# Enerfi.net
KiCad netlist of a schematic drawn in Altium Designer
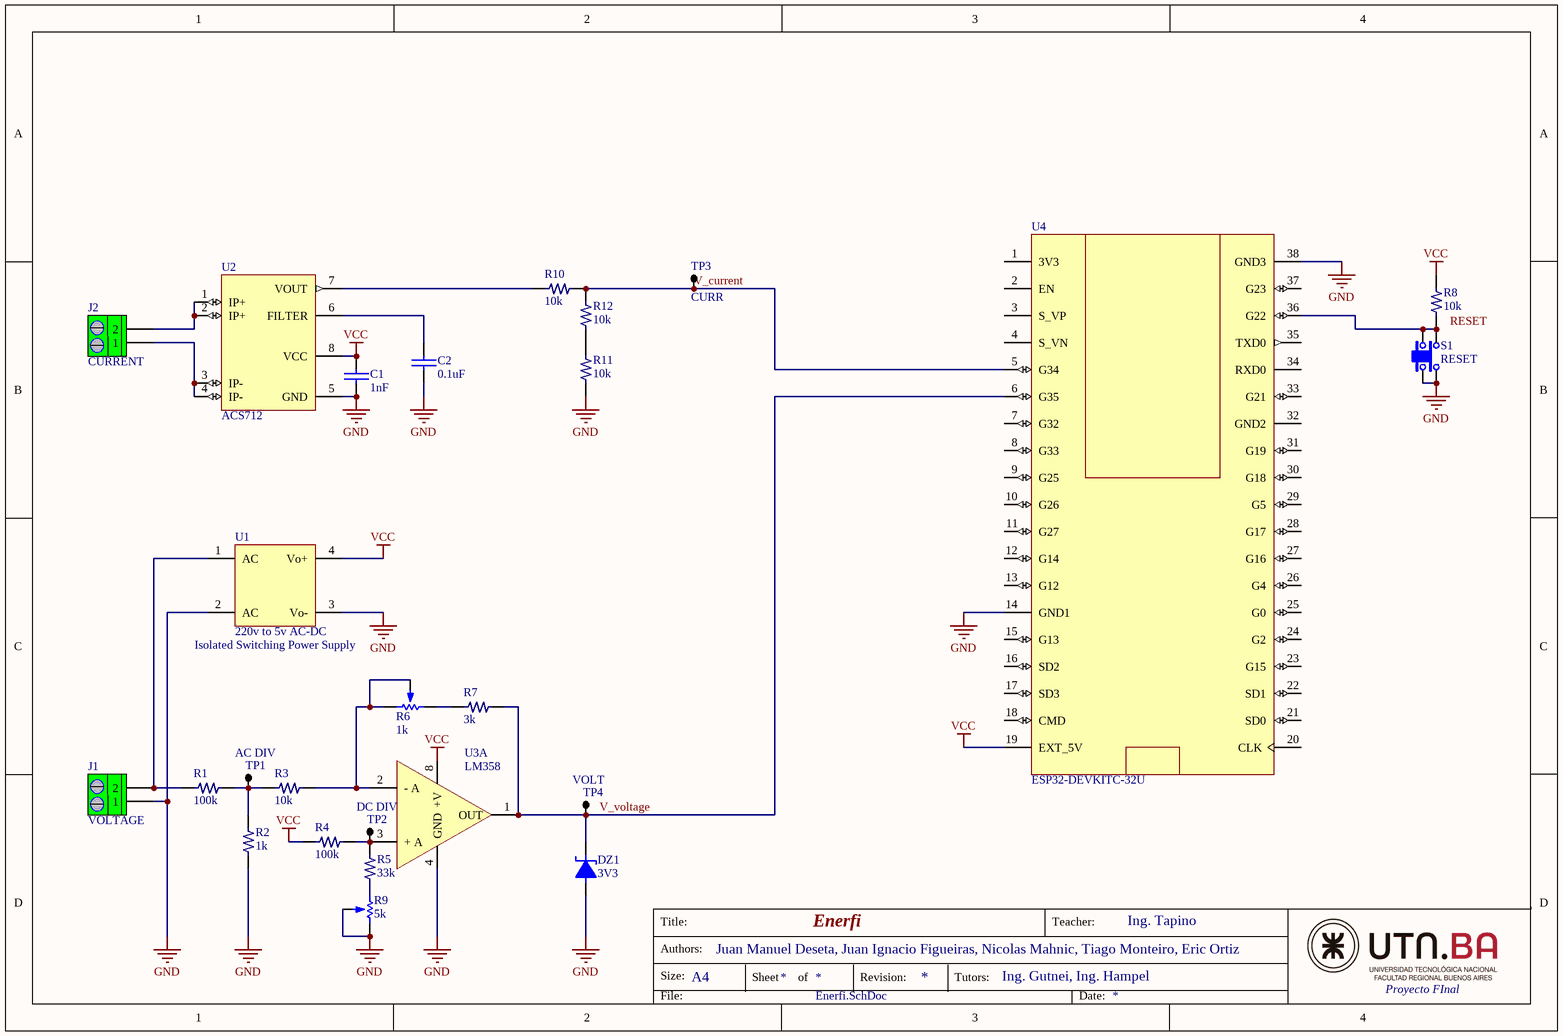
[diagram p0: Enerfi.SchDoc]

(export (version "E")
  (design (tool "Eeschema 10.0.6"))
  (components
    (comp (ref "C1") (value "1nF") (footprint "C0805-0.80") (libsource (lib "EnerfiLib") (part "CAP")))
    (comp (ref "C2") (value "0.1uF") (footprint "C0805-0.80") (libsource (lib "EnerfiLib") (part "CAP")))
    (comp (ref "DZ1") (value "3V3") (footprint "DO35") (libsource (lib "EnerfiLib") (part "DIODO ZENER")))
    (comp (ref "J1")
      (value "VOLTAGE")
      (footprint "BORNERA2")
      (libsource (lib "EnerfiLib") (part "BORNERA 2_V"))
    )
    (comp (ref "J2")
      (value "CURRENT")
      (footprint "BORNERA2")
      (libsource (lib "EnerfiLib") (part "BORNERA 2_V"))
    )
    (comp (ref "R1") (value "100k") (footprint "R0805-0.45") (libsource (lib "EnerfiLib") (part "RES_1")))
    (comp (ref "R2") (value "1k") (footprint "R0805-0.45") (libsource (lib "EnerfiLib") (part "RES_1")))
    (comp (ref "R3") (value "10k") (footprint "R0805-0.45") (libsource (lib "EnerfiLib") (part "RES_1")))
    (comp (ref "R4") (value "100k") (footprint "R0805-0.45") (libsource (lib "EnerfiLib") (part "RES_1")))
    (comp (ref "R5") (value "33k") (footprint "R0805-0.45") (libsource (lib "EnerfiLib") (part "RES_1")))
    (comp (ref "R6") (value "1k") (footprint "PRESET V") (libsource (lib "EnerfiLib") (part "Preset")))
    (comp (ref "R7") (value "3k") (footprint "R0805-0.45") (libsource (lib "EnerfiLib") (part "RES_1")))
    (comp (ref "R8") (value "10k") (footprint "R0805-0.45") (libsource (lib "EnerfiLib") (part "RES_1")))
    (comp (ref "R9") (value "5k") (footprint "PRESET V") (libsource (lib "EnerfiLib") (part "Preset")))
    (comp (ref "R10") (value "10k") (footprint "R0805-0.45") (libsource (lib "EnerfiLib") (part "RES_1")))
    (comp (ref "R11") (value "10k") (footprint "R0805-0.45") (libsource (lib "EnerfiLib") (part "RES_1")))
    (comp (ref "R12") (value "10k") (footprint "R0805-0.45") (libsource (lib "EnerfiLib") (part "RES_1")))
    (comp (ref "S1") (value "RESET") (footprint "TACTSWITCH") (libsource (lib "EnerfiLib") (part "TACT SW")))
    (comp (ref "TP1") (value "AC DIV") (footprint "TPTH") (libsource (lib "EnerfiLib") (part "TP")))
    (comp (ref "TP2") (value "DC DIV") (footprint "TPTH") (libsource (lib "EnerfiLib") (part "TP")))
    (comp (ref "TP3") (value "CURR") (footprint "TPTH") (libsource (lib "EnerfiLib") (part "TP")))
    (comp (ref "TP4") (value "VOLT") (footprint "TPTH") (libsource (lib "EnerfiLib") (part "TP")))
    (comp (ref "U1")
      (value "220v to 5v AC-DC")
      (footprint "HLK PM01")
      (description "HLK PM01 220v to 5v AC-DC Isolated Switching Power Supply")
      (fields (field (name "AUTOR") "Nicolas Mahnic"))
      (libsource (lib "EnerfiLib") (part "HLK PM01"))
    )
    (comp (ref "U2")
      (value "ACS712")
      (footprint "SOP127P600X175-8N")
      (description "Hall Effect-Based Linear Current Sensor")
      (fields (field (name "AUTOR") "Nicolas Mahnic"))
      (libsource (lib "EnerfiLib") (part "ACS712"))
    )
    (comp (ref "U3")
      (value "LM358")
      (footprint "SOP127P600X175-8N")
      (libsource (lib "EnerfiLib") (part "LM358"))
    )
    (comp (ref "U4")
      (value "ESP32-DEVKITC-32U")
      (footprint "MODULE_ESP32_DEVKIT_V1")
      (fields (field (name "MF") "Espressif Systems") (field (name "AUTOR") "Nicolas Mahnic"))
      (libsource (lib "EnerfiLib") (part "ESP32-DEVKITC-32U"))
    )
  )
  (nets
    (net (code "2") (name "/V_current") (class "Default")
      (node (ref "R10") (pin "2") (pinfunction "2_2") (pintype "passive"))
      (node (ref "R12") (pin "2") (pinfunction "2_2") (pintype "passive"))
      (node (ref "TP3") (pin "1") (pinfunction "1_1") (pintype "passive"))
      (node (ref "U4") (pin "5") (pinfunction "G34_5") (pintype "bidirectional"))
    )
    (net (code "3") (name "/V_voltage") (class "Default")
      (node (ref "DZ1") (pin "2") (pinfunction "2_2") (pintype "passive"))
      (node (ref "R7") (pin "2") (pinfunction "2_2") (pintype "passive"))
      (node (ref "TP4") (pin "1") (pinfunction "1_1") (pintype "passive"))
      (node (ref "U3") (pin "1") (pinfunction "OUT_1") (pintype "passive"))
      (node (ref "U4") (pin "6") (pinfunction "G35_6") (pintype "bidirectional"))
    )
    (net (code "4") (name "GND") (class "Default")
      (node (ref "C1") (pin "2") (pinfunction "2_2") (pintype "passive"))
      (node (ref "C2") (pin "2") (pinfunction "2_2") (pintype "passive"))
      (node (ref "DZ1") (pin "1") (pinfunction "1_1") (pintype "passive"))
      (node (ref "J1") (pin "1") (pinfunction "1_1") (pintype "passive"))
      (node (ref "R11") (pin "1") (pinfunction "1_1") (pintype "passive"))
      (node (ref "R2") (pin "1") (pinfunction "1_1") (pintype "passive"))
      (node (ref "R9") (pin "1") (pinfunction "1_1") (pintype "passive"))
      (node (ref "R9") (pin "2") (pinfunction "2_2") (pintype "passive"))
      (node (ref "S1") (pin "1") (pinfunction "1_1") (pintype "passive"))
      (node (ref "S1") (pin "2") (pinfunction "2_2") (pintype "passive"))
      (node (ref "U1") (pin "2") (pinfunction "AC_2") (pintype "power_in"))
      (node (ref "U1") (pin "3") (pinfunction "Vo-_3") (pintype "power_in"))
      (node (ref "U2") (pin "5") (pinfunction "GND_5") (pintype "power_in"))
      (node (ref "U3") (pin "4") (pinfunction "GND_4") (pintype "passive"))
      (node (ref "U4") (pin "14") (pinfunction "GND1_14") (pintype "power_in"))
      (node (ref "U4") (pin "38") (pinfunction "GND3_38") (pintype "power_in"))
    )
    (net (code "5") (name "Net-(J1-Pad2)") (class "Default")
      (node (ref "J1") (pin "2") (pinfunction "2_2") (pintype "passive"))
      (node (ref "R1") (pin "1") (pinfunction "1_1") (pintype "passive"))
      (node (ref "U1") (pin "1") (pinfunction "AC_1") (pintype "power_in"))
    )
    (net (code "6") (name "Net-(J2-Pad1)") (class "Default")
      (node (ref "J2") (pin "1") (pinfunction "1_1") (pintype "passive"))
      (node (ref "U2") (pin "3") (pinfunction "IP-_3") (pintype "bidirectional"))
      (node (ref "U2") (pin "4") (pinfunction "IP-_4") (pintype "bidirectional"))
    )
    (net (code "7") (name "Net-(J2-Pad2)") (class "Default")
      (node (ref "J2") (pin "2") (pinfunction "2_2") (pintype "passive"))
      (node (ref "U2") (pin "1") (pinfunction "IP+_1") (pintype "bidirectional"))
      (node (ref "U2") (pin "2") (pinfunction "IP+_2") (pintype "bidirectional"))
    )
    (net (code "8") (name "Net-(R1-Pad2)") (class "Default")
      (node (ref "R1") (pin "2") (pinfunction "2_2") (pintype "passive"))
      (node (ref "R2") (pin "2") (pinfunction "2_2") (pintype "passive"))
      (node (ref "R3") (pin "1") (pinfunction "1_1") (pintype "passive"))
      (node (ref "TP1") (pin "1") (pinfunction "1_1") (pintype "passive"))
    )
    (net (code "9") (name "Net-(R5-Pad1)") (class "Default")
      (node (ref "R5") (pin "1") (pinfunction "1_1") (pintype "passive"))
      (node (ref "R9") (pin "3") (pinfunction "3_3") (pintype "passive"))
    )
    (net (code "10") (name "Net-(R6-Pad3)") (class "Default")
      (node (ref "R6") (pin "3") (pinfunction "3_3") (pintype "passive"))
      (node (ref "R7") (pin "1") (pinfunction "1_1") (pintype "passive"))
    )
    (net (code "11") (name "Net-(R11-Pad2)") (class "Default")
      (node (ref "R11") (pin "2") (pinfunction "2_2") (pintype "passive"))
      (node (ref "R12") (pin "1") (pinfunction "1_1") (pintype "passive"))
    )
    (net (code "12") (name "Net-(U2-FILTER)") (class "Default")
      (node (ref "C2") (pin "1") (pinfunction "1_1") (pintype "passive"))
      (node (ref "U2") (pin "6") (pinfunction "FILTER_6") (pintype "passive"))
    )
    (net (code "13") (name "Net-(U2-VOUT)") (class "Default")
      (node (ref "R10") (pin "1") (pinfunction "1_1") (pintype "passive"))
      (node (ref "U2") (pin "7") (pinfunction "VOUT_7") (pintype "output"))
    )
    (net (code "14") (name "Net-(U3A-+_A)") (class "Default")
      (node (ref "R4") (pin "2") (pinfunction "2_2") (pintype "passive"))
      (node (ref "R5") (pin "2") (pinfunction "2_2") (pintype "passive"))
      (node (ref "TP2") (pin "1") (pinfunction "1_1") (pintype "passive"))
      (node (ref "U3") (pin "3") (pinfunction "+_A_3") (pintype "passive"))
    )
    (net (code "15") (name "Net-(U3A--_A)") (class "Default")
      (node (ref "R3") (pin "2") (pinfunction "2_2") (pintype "passive"))
      (node (ref "R6") (pin "1") (pinfunction "1_1") (pintype "passive"))
      (node (ref "R6") (pin "2") (pinfunction "2_2") (pintype "passive"))
      (node (ref "U3") (pin "2") (pinfunction "-_A_2") (pintype "passive"))
    )
    (net (code "16") (name "Net-(U4-G22)") (class "Default")
      (node (ref "R8") (pin "1") (pinfunction "1_1") (pintype "passive"))
      (node (ref "S1") (pin "3") (pinfunction "3_3") (pintype "passive"))
      (node (ref "S1") (pin "4") (pinfunction "4_4") (pintype "passive"))
      (node (ref "U4") (pin "36") (pinfunction "G22_36") (pintype "bidirectional"))
    )
    (net (code "17") (name "VCC") (class "Default")
      (node (ref "C1") (pin "1") (pinfunction "1_1") (pintype "passive"))
      (node (ref "R4") (pin "1") (pinfunction "1_1") (pintype "passive"))
      (node (ref "R8") (pin "2") (pinfunction "2_2") (pintype "passive"))
      (node (ref "U1") (pin "4") (pinfunction "Vo+_4") (pintype "power_in"))
      (node (ref "U2") (pin "8") (pinfunction "VCC_8") (pintype "power_in"))
      (node (ref "U3") (pin "8") (pinfunction "+V_8") (pintype "passive"))
      (node (ref "U4") (pin "19") (pinfunction "EXT_5V_19") (pintype "power_in"))
    )
    (net (code "18") (name "unconnected-(U4-3V3-Pad1)") (class "Default")
      (node (ref "U4") (pin "1") (pinfunction "3V3_1") (pintype "power_in"))
    )
    (net (code "19") (name "unconnected-(U4-CLK-Pad20)") (class "Default")
      (node (ref "U4") (pin "20") (pinfunction "CLK_20") (pintype "tri_state"))
    )
    (net (code "20") (name "unconnected-(U4-CMD-Pad18)") (class "Default")
      (node (ref "U4") (pin "18") (pinfunction "CMD_18") (pintype "bidirectional"))
    )
    (net (code "21") (name "unconnected-(U4-EN-Pad2)") (class "Default")
      (node (ref "U4") (pin "2") (pinfunction "EN_2") (pintype "tri_state"))
    )
    (net (code "22") (name "unconnected-(U4-G0-Pad25)") (class "Default")
      (node (ref "U4") (pin "25") (pinfunction "G0_25") (pintype "bidirectional"))
    )
    (net (code "23") (name "unconnected-(U4-G2-Pad24)") (class "Default")
      (node (ref "U4") (pin "24") (pinfunction "G2_24") (pintype "bidirectional"))
    )
    (net (code "24") (name "unconnected-(U4-G4-Pad26)") (class "Default")
      (node (ref "U4") (pin "26") (pinfunction "G4_26") (pintype "bidirectional"))
    )
    (net (code "25") (name "unconnected-(U4-G5-Pad29)") (class "Default")
      (node (ref "U4") (pin "29") (pinfunction "G5_29") (pintype "bidirectional"))
    )
    (net (code "26") (name "unconnected-(U4-G12-Pad13)") (class "Default")
      (node (ref "U4") (pin "13") (pinfunction "G12_13") (pintype "bidirectional"))
    )
    (net (code "27") (name "unconnected-(U4-G13-Pad15)") (class "Default")
      (node (ref "U4") (pin "15") (pinfunction "G13_15") (pintype "bidirectional"))
    )
    (net (code "28") (name "unconnected-(U4-G14-Pad12)") (class "Default")
      (node (ref "U4") (pin "12") (pinfunction "G14_12") (pintype "bidirectional"))
    )
    (net (code "29") (name "unconnected-(U4-G15-Pad23)") (class "Default")
      (node (ref "U4") (pin "23") (pinfunction "G15_23") (pintype "bidirectional"))
    )
    (net (code "30") (name "unconnected-(U4-G16-Pad27)") (class "Default")
      (node (ref "U4") (pin "27") (pinfunction "G16_27") (pintype "bidirectional"))
    )
    (net (code "31") (name "unconnected-(U4-G17-Pad28)") (class "Default")
      (node (ref "U4") (pin "28") (pinfunction "G17_28") (pintype "bidirectional"))
    )
    (net (code "32") (name "unconnected-(U4-G18-Pad30)") (class "Default")
      (node (ref "U4") (pin "30") (pinfunction "G18_30") (pintype "bidirectional"))
    )
    (net (code "33") (name "unconnected-(U4-G19-Pad31)") (class "Default")
      (node (ref "U4") (pin "31") (pinfunction "G19_31") (pintype "bidirectional"))
    )
    (net (code "34") (name "unconnected-(U4-G21-Pad33)") (class "Default")
      (node (ref "U4") (pin "33") (pinfunction "G21_33") (pintype "bidirectional"))
    )
    (net (code "35") (name "unconnected-(U4-G23-Pad37)") (class "Default")
      (node (ref "U4") (pin "37") (pinfunction "G23_37") (pintype "bidirectional"))
    )
    (net (code "36") (name "unconnected-(U4-G25-Pad9)") (class "Default")
      (node (ref "U4") (pin "9") (pinfunction "G25_9") (pintype "bidirectional"))
    )
    (net (code "37") (name "unconnected-(U4-G26-Pad10)") (class "Default")
      (node (ref "U4") (pin "10") (pinfunction "G26_10") (pintype "bidirectional"))
    )
    (net (code "38") (name "unconnected-(U4-G27-Pad11)") (class "Default")
      (node (ref "U4") (pin "11") (pinfunction "G27_11") (pintype "bidirectional"))
    )
    (net (code "39") (name "unconnected-(U4-G32-Pad7)") (class "Default")
      (node (ref "U4") (pin "7") (pinfunction "G32_7") (pintype "bidirectional"))
    )
    (net (code "40") (name "unconnected-(U4-G33-Pad8)") (class "Default")
      (node (ref "U4") (pin "8") (pinfunction "G33_8") (pintype "bidirectional"))
    )
    (net (code "41") (name "unconnected-(U4-GND2-Pad32)") (class "Default")
      (node (ref "U4") (pin "32") (pinfunction "GND2_32") (pintype "power_in"))
    )
    (net (code "42") (name "unconnected-(U4-RXD0-Pad34)") (class "Default")
      (node (ref "U4") (pin "34") (pinfunction "RXD0_34") (pintype "tri_state"))
    )
    (net (code "43") (name "unconnected-(U4-SD0-Pad21)") (class "Default")
      (node (ref "U4") (pin "21") (pinfunction "SD0_21") (pintype "bidirectional"))
    )
    (net (code "44") (name "unconnected-(U4-SD1-Pad22)") (class "Default")
      (node (ref "U4") (pin "22") (pinfunction "SD1_22") (pintype "bidirectional"))
    )
    (net (code "45") (name "unconnected-(U4-SD2-Pad16)") (class "Default")
      (node (ref "U4") (pin "16") (pinfunction "SD2_16") (pintype "bidirectional"))
    )
    (net (code "46") (name "unconnected-(U4-SD3-Pad17)") (class "Default")
      (node (ref "U4") (pin "17") (pinfunction "SD3_17") (pintype "bidirectional"))
    )
    (net (code "47") (name "unconnected-(U4-S_VN-Pad4)") (class "Default")
      (node (ref "U4") (pin "4") (pinfunction "S_VN_4") (pintype "tri_state"))
    )
    (net (code "48") (name "unconnected-(U4-S_VP-Pad3)") (class "Default")
      (node (ref "U4") (pin "3") (pinfunction "S_VP_3") (pintype "tri_state"))
    )
    (net (code "49") (name "unconnected-(U4-TXD0-Pad35)") (class "Default")
      (node (ref "U4") (pin "35") (pinfunction "TXD0_35") (pintype "output"))
    )
  )
)
